# schematic.net
KiCad netlist of a schematic drawn in EAGLE
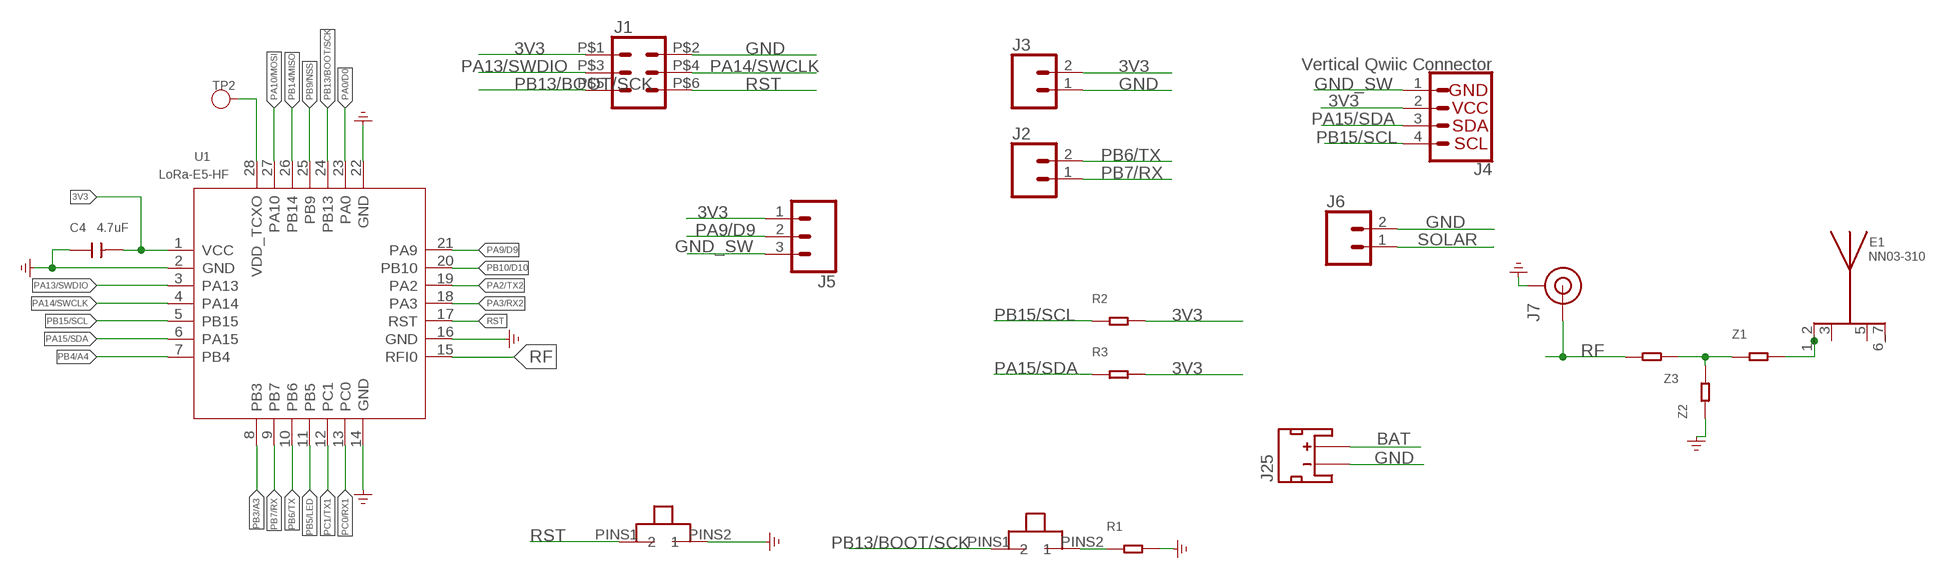
[diagram p0: schematic, sheet 1]
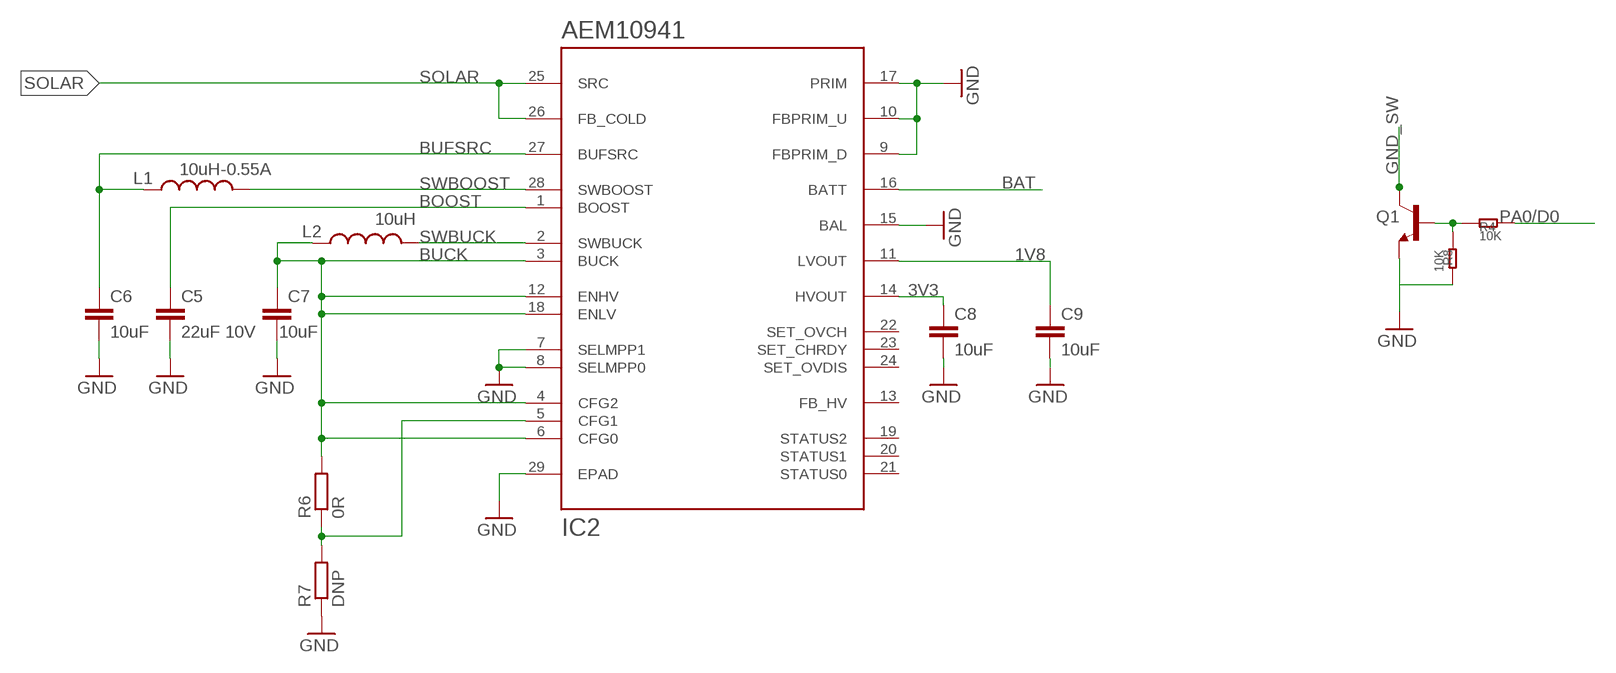
[diagram p1: schematic, sheet 2]

(export (version "E")
  (design (tool "Eeschema 10.0.6"))
  (components
    (comp (ref "C4")
      (value "4.7uF")
      (footprint "eagle-import:C0603")
      (libsource (lib "eagle-import") (part "CAP-0603"))
    )
    (comp (ref "E1")
      (value "NN03-310")
      (footprint "eagle-import:XCVR_NN03-310")
      (fields (field (name "MF") "Ignion"))
      (libsource (lib "eagle-import") (part "NN03-310"))
    )
    (comp (ref "J1")
      (value "CONN_03X2POGO_PINS")
      (footprint "eagle-import:2X3_POGO")
      (libsource (lib "eagle-import") (part "CONN_03X2POGO_PINS"))
    )
    (comp (ref "J2")
      (value "CONN_02")
      (footprint "eagle-import:1X02")
      (libsource (lib "eagle-import") (part "CONN_02"))
    )
    (comp (ref "J3")
      (value "CONN_02")
      (footprint "eagle-import:1X02")
      (libsource (lib "eagle-import") (part "CONN_02"))
    )
    (comp (ref "J4")
      (value "Vertical Qwiic Connector")
      (footprint "eagle-import:JST04_1MM_VERT")
      (libsource (lib "eagle-import") (part "QWIIC_CONNECTOR"))
    )
    (comp (ref "J5")
      (value "CONN_031X03_NO_SILK")
      (footprint "eagle-import:1X03_NO_SILK")
      (libsource (lib "eagle-import") (part "CONN_031X03_NO_SILK"))
    )
    (comp (ref "J6")
      (value "CONN_02")
      (footprint "eagle-import:1X02")
      (libsource (lib "eagle-import") (part "CONN_02"))
    )
    (comp (ref "J7")
      (value "U.FL2PIN-REDUCED-FOOTPRINT")
      (footprint "eagle-import:U.FL_REDUCED_FOOTPRINT")
      (libsource (lib "eagle-import") (part "U.FL2PIN-REDUCED-FOOTPRINT"))
    )
    (comp (ref "J25")
      (value "JST_2MM_MALE")
      (footprint "eagle-import:JST-2-SMD")
      (libsource (lib "eagle-import") (part "JST_2MM_MALE"))
    )
    (comp (ref "R1")
      (value "RES-0603")
      (footprint "eagle-import:R0603")
      (libsource (lib "eagle-import") (part "RES-0603"))
    )
    (comp (ref "R2")
      (value "RES-0603")
      (footprint "eagle-import:R0603")
      (libsource (lib "eagle-import") (part "RES-0603"))
    )
    (comp (ref "R3")
      (value "RES-0603")
      (footprint "eagle-import:R0603")
      (libsource (lib "eagle-import") (part "RES-0603"))
    )
    (comp (ref "TP2")
      (value "TEST")
      (footprint "eagle-import:TP-D45MIL")
      (fields (field (name "PARTNO") "DNP"))
      (libsource (lib "eagle-import") (part "TEST-POINT'4545'"))
    )
    (comp (ref "U$1")
      (value "TACTILE")
      (footprint "eagle-import:TACTILE")
      (libsource (lib "eagle-import") (part "TACTILE"))
    )
    (comp (ref "U$2")
      (value "TACTILE")
      (footprint "eagle-import:TACTILE")
      (libsource (lib "eagle-import") (part "TACTILE"))
    )
    (comp (ref "U1")
      (value "LoRa-E5-HF")
      (footprint "eagle-import:MOUDLE28P-1.25-12X12X2.5MM")
      (libsource (lib "eagle-import") (part "MOUDLE_LORA_E5"))
    )
    (comp (ref "Z1")
      (value "RES-0603")
      (footprint "eagle-import:R0603")
      (libsource (lib "eagle-import") (part "RES-0603"))
    )
    (comp (ref "Z2")
      (value "RES-0603")
      (footprint "eagle-import:R0603")
      (libsource (lib "eagle-import") (part "RES-0603"))
    )
    (comp (ref "Z3")
      (value "RES-0603")
      (footprint "eagle-import:R0603")
      (libsource (lib "eagle-import") (part "RES-0603"))
    )
    (comp (ref "C5")
      (value "22uF 10V")
      (footprint "eagle-import:C0603")
      (fields
        (field (name "MF") "Murata")
        (field (name "MPN") "GRM188R61A226ME15D")
        (field (name "MF_1") "TDK")
        (field (name "MPN_1") "CGA5L1X7S1A226M160AC")
      )
      (libsource (lib "eagle-import") (part "C0603_22UF"))
    )
    (comp (ref "C6")
      (value "10uF")
      (footprint "eagle-import:C0603")
      (fields
        (field (name "MF") "Taiyo Yuden")
        (field (name "MPN") "LMK107BBJ106MALT")
        (field (name "MF_1") "KEYSTONE")
        (field (name "MPN_1") "1049P")
      )
      (libsource (lib "eagle-import") (part "C0603_10UF"))
    )
    (comp (ref "C7")
      (value "10uF")
      (footprint "eagle-import:C0603")
      (fields
        (field (name "MF") "Taiyo Yuden")
        (field (name "MPN") "LMK107BBJ106MALT")
        (field (name "MF_1") "KEYSTONE")
        (field (name "MPN_1") "1049P")
      )
      (libsource (lib "eagle-import") (part "C0603_10UF"))
    )
    (comp (ref "C8")
      (value "10uF")
      (footprint "eagle-import:C0603")
      (fields
        (field (name "MF") "Taiyo Yuden")
        (field (name "MPN") "LMK107BBJ106MALT")
        (field (name "MF_1") "KEYSTONE")
        (field (name "MPN_1") "1049P")
      )
      (libsource (lib "eagle-import") (part "C0603_10UF"))
    )
    (comp (ref "C9")
      (value "10uF")
      (footprint "eagle-import:C0603")
      (fields
        (field (name "MF") "Taiyo Yuden")
        (field (name "MPN") "LMK107BBJ106MALT")
        (field (name "MF_1") "KEYSTONE")
        (field (name "MPN_1") "1049P")
      )
      (libsource (lib "eagle-import") (part "C0603_10UF"))
    )
    (comp (ref "IC2")
      (value "AEM10941")
      (footprint "eagle-import:QFN50P505X505X90-28")
      (fields (field (name "MF") "e-peas"))
      (libsource (lib "eagle-import") (part "AEM10941"))
    )
    (comp (ref "L1")
      (value "10uH-0.55A")
      (footprint "eagle-import:LPS4012")
      (fields
        (field (name "MF") "Coilcraft")
        (field (name "MPN") "LPS4012-103MRB")
        (field (name "MF_1") "BOURNS")
        (field (name "MPN_1") "SRN2009T-100M")
      )
      (libsource (lib "eagle-import") (part "L3.9X3.9_10UH_0.55A"))
    )
    (comp (ref "L2")
      (value "10uH")
      (footprint "eagle-import:L0603")
      (fields
        (field (name "MF") "TDK")
        (field (name "MPN") "MLZ1608M100WT")
        (field (name "MF_1") "TAIYO YUDEN")
        (field (name "MPN_1") "CK2125100M-T")
      )
      (libsource (lib "eagle-import") (part "L0603_10UH"))
    )
    (comp (ref "Q1")
      (value "500mA/300V")
      (footprint "eagle-import:SOT23-3")
      (libsource (lib "eagle-import") (part "TRANS_NPN-MMBTA42"))
    )
    (comp (ref "R4")
      (value "10K")
      (footprint "eagle-import:R0603")
      (libsource (lib "eagle-import") (part "RES-0603"))
    )
    (comp (ref "R6")
      (value "0R")
      (footprint "eagle-import:R0402")
      (fields (field (name "MF") "Walsin") (field (name "MPN") "WR04X1004FTL"))
      (libsource (lib "eagle-import") (part "R0402_1M"))
    )
    (comp (ref "R7")
      (value "DNP")
      (footprint "eagle-import:R0402")
      (fields (field (name "MF") "Walsin") (field (name "MPN") "WR04X1004FTL"))
      (libsource (lib "eagle-import") (part "R0402_1M"))
    )
    (comp (ref "R8")
      (value "10K")
      (footprint "eagle-import:R0603")
      (libsource (lib "eagle-import") (part "RES-0603"))
    )
  )
  (nets
    (net (code "1") (name "1V8") (class "Default")
      (node (ref "C9") (pin "1") (pinfunction "1_1") (pintype "passive"))
      (node (ref "IC2") (pin "11") (pinfunction "LVOUT_11") (pintype "bidirectional"))
    )
    (net (code "2") (name "3V3") (class "Default")
      (node (ref "C4") (pin "2") (pinfunction "2_2") (pintype "passive"))
      (node (ref "C8") (pin "1") (pinfunction "1_1") (pintype "passive"))
      (node (ref "IC2") (pin "14") (pinfunction "HVOUT_14") (pintype "bidirectional"))
      (node (ref "J1") (pin "P$1") (pinfunction "1_P$1") (pintype "bidirectional"))
      (node (ref "J3") (pin "2") (pinfunction "2_2") (pintype "passive"))
      (node (ref "J4") (pin "2") (pinfunction "2_2") (pintype "power_in"))
      (node (ref "J5") (pin "1") (pinfunction "1_1") (pintype "passive"))
      (node (ref "R2") (pin "2") (pinfunction "2_2") (pintype "passive"))
      (node (ref "R3") (pin "2") (pinfunction "2_2") (pintype "passive"))
      (node (ref "U1") (pin "1") (pinfunction "VCC_1") (pintype "bidirectional"))
    )
    (net (code "3") (name "BAT") (class "Default")
      (node (ref "IC2") (pin "16") (pinfunction "BATT_16") (pintype "bidirectional"))
      (node (ref "J25") (pin "2") (pinfunction "+_2") (pintype "bidirectional"))
    )
    (net (code "4") (name "BOOST") (class "Default")
      (node (ref "C5") (pin "1") (pinfunction "1_1") (pintype "passive"))
      (node (ref "IC2") (pin "1") (pinfunction "BOOST_1") (pintype "bidirectional"))
    )
    (net (code "5") (name "BUCK") (class "Default")
      (node (ref "C7") (pin "1") (pinfunction "1_1") (pintype "passive"))
      (node (ref "IC2") (pin "12") (pinfunction "ENHV_12") (pintype "bidirectional"))
      (node (ref "IC2") (pin "18") (pinfunction "ENLV_18") (pintype "bidirectional"))
      (node (ref "IC2") (pin "3") (pinfunction "BUCK_3") (pintype "bidirectional"))
      (node (ref "IC2") (pin "4") (pinfunction "CFG2_4") (pintype "bidirectional"))
      (node (ref "IC2") (pin "6") (pinfunction "CFG0_6") (pintype "bidirectional"))
      (node (ref "L2") (pin "1") (pinfunction "1_1") (pintype "passive"))
      (node (ref "R6") (pin "2") (pinfunction "2_2") (pintype "passive"))
    )
    (net (code "6") (name "BUFSRC") (class "Default")
      (node (ref "C6") (pin "1") (pinfunction "1_1") (pintype "passive"))
      (node (ref "IC2") (pin "27") (pinfunction "BUFSRC_27") (pintype "power_in"))
      (node (ref "L1") (pin "1") (pinfunction "1_1") (pintype "passive"))
    )
    (net (code "7") (name "GND") (class "Default")
      (node (ref "C4") (pin "1") (pinfunction "1_1") (pintype "passive"))
      (node (ref "C5") (pin "2") (pinfunction "2_2") (pintype "passive"))
      (node (ref "C6") (pin "2") (pinfunction "2_2") (pintype "passive"))
      (node (ref "C7") (pin "2") (pinfunction "2_2") (pintype "passive"))
      (node (ref "C8") (pin "2") (pinfunction "2_2") (pintype "passive"))
      (node (ref "C9") (pin "2") (pinfunction "2_2") (pintype "passive"))
      (node (ref "IC2") (pin "10") (pinfunction "FBPRIM_U_10") (pintype "bidirectional"))
      (node (ref "IC2") (pin "15") (pinfunction "BAL_15") (pintype "bidirectional"))
      (node (ref "IC2") (pin "17") (pinfunction "PRIM_17") (pintype "bidirectional"))
      (node (ref "IC2") (pin "29") (pinfunction "EPAD_29") (pintype "power_in"))
      (node (ref "IC2") (pin "7") (pinfunction "SELMPP1_7") (pintype "bidirectional"))
      (node (ref "IC2") (pin "8") (pinfunction "SELMPP0_8") (pintype "bidirectional"))
      (node (ref "IC2") (pin "9") (pinfunction "FBPRIM_D_9") (pintype "bidirectional"))
      (node (ref "J1") (pin "P$2") (pinfunction "2_P$2") (pintype "bidirectional"))
      (node (ref "J25") (pin "1") (pinfunction "-_1") (pintype "bidirectional"))
      (node (ref "J3") (pin "1") (pinfunction "1_1") (pintype "passive"))
      (node (ref "J6") (pin "2") (pinfunction "2_2") (pintype "passive"))
      (node (ref "J7") (pin "1") (pinfunction "GND_1") (pintype "bidirectional"))
      (node (ref "J7") (pin "2") (pinfunction "GND_2") (pintype "bidirectional"))
      (node (ref "Q1") (pin "2") (pinfunction "E_2") (pintype "passive"))
      (node (ref "R1") (pin "2") (pinfunction "2_2") (pintype "passive"))
      (node (ref "R7") (pin "1") (pinfunction "1_1") (pintype "passive"))
      (node (ref "R8") (pin "2") (pinfunction "2_2") (pintype "passive"))
      (node (ref "U$1") (pin "PINS2") (pinfunction "2_PINS2") (pintype "bidirectional"))
      (node (ref "U1") (pin "14") (pinfunction "GND_14") (pintype "bidirectional"))
      (node (ref "U1") (pin "16") (pinfunction "GND_16") (pintype "bidirectional"))
      (node (ref "U1") (pin "2") (pinfunction "GND_2") (pintype "bidirectional"))
      (node (ref "U1") (pin "22") (pinfunction "GND_22") (pintype "bidirectional"))
      (node (ref "Z2") (pin "1") (pinfunction "1_1") (pintype "passive"))
    )
    (net (code "8") (name "GND_SW") (class "Default")
      (node (ref "J4") (pin "1") (pinfunction "1_1") (pintype "power_in"))
      (node (ref "J5") (pin "3") (pinfunction "3_3") (pintype "passive"))
      (node (ref "Q1") (pin "3") (pinfunction "C_3") (pintype "passive"))
    )
    (net (code "9") (name "Net-(E1-1)") (class "Default")
      (node (ref "E1") (pin "1_2") (pinfunction "1_1_2") (pintype "input"))
      (node (ref "Z1") (pin "2") (pinfunction "2_2") (pintype "passive"))
    )
    (net (code "10") (name "Net-(IC2-CFG1)") (class "Default")
      (node (ref "IC2") (pin "5") (pinfunction "CFG1_5") (pintype "bidirectional"))
      (node (ref "R6") (pin "1") (pinfunction "1_1") (pintype "passive"))
      (node (ref "R7") (pin "2") (pinfunction "2_2") (pintype "passive"))
    )
    (net (code "11") (name "Net-(Q1-B)") (class "Default")
      (node (ref "Q1") (pin "1") (pinfunction "B_1") (pintype "passive"))
      (node (ref "R4") (pin "1") (pinfunction "1_1") (pintype "passive"))
      (node (ref "R8") (pin "1") (pinfunction "1_1") (pintype "passive"))
    )
    (net (code "12") (name "Net-(U$2-2)") (class "Default")
      (node (ref "R1") (pin "1") (pinfunction "1_1") (pintype "passive"))
      (node (ref "U$2") (pin "PINS2") (pinfunction "2_PINS2") (pintype "bidirectional"))
    )
    (net (code "13") (name "Net-(U1-VDD_TCXO)") (class "Default")
      (node (ref "TP2") (pin "T") (pinfunction "T_T") (pintype "bidirectional"))
      (node (ref "U1") (pin "28") (pinfunction "VDD_TCXO_28") (pintype "bidirectional"))
    )
    (net (code "14") (name "Net-(Z1-Pad1)") (class "Default")
      (node (ref "Z1") (pin "1") (pinfunction "1_1") (pintype "passive"))
      (node (ref "Z2") (pin "2") (pinfunction "2_2") (pintype "passive"))
      (node (ref "Z3") (pin "1") (pinfunction "1_1") (pintype "passive"))
    )
    (net (code "15") (name "PA0{slash}D0") (class "Default")
      (node (ref "R4") (pin "2") (pinfunction "2_2") (pintype "passive"))
      (node (ref "U1") (pin "23") (pinfunction "PA0_23") (pintype "bidirectional"))
    )
    (net (code "16") (name "PA2{slash}TX2") (class "Default")
      (node (ref "U1") (pin "19") (pinfunction "PA2_19") (pintype "bidirectional"))
    )
    (net (code "17") (name "PA3{slash}RX2") (class "Default")
      (node (ref "U1") (pin "18") (pinfunction "PA3_18") (pintype "bidirectional"))
    )
    (net (code "18") (name "PA9{slash}D9") (class "Default")
      (node (ref "J5") (pin "2") (pinfunction "2_2") (pintype "passive"))
      (node (ref "U1") (pin "21") (pinfunction "PA9_21") (pintype "bidirectional"))
    )
    (net (code "19") (name "PA10{slash}MOSI") (class "Default")
      (node (ref "U1") (pin "27") (pinfunction "PA10_27") (pintype "bidirectional"))
    )
    (net (code "20") (name "PA13{slash}SWDIO") (class "Default")
      (node (ref "J1") (pin "P$3") (pinfunction "3_P$3") (pintype "bidirectional"))
      (node (ref "U1") (pin "3") (pinfunction "PA13_3") (pintype "bidirectional"))
    )
    (net (code "21") (name "PA14{slash}SWCLK") (class "Default")
      (node (ref "J1") (pin "P$4") (pinfunction "4_P$4") (pintype "bidirectional"))
      (node (ref "U1") (pin "4") (pinfunction "PA14_4") (pintype "bidirectional"))
    )
    (net (code "22") (name "PA15{slash}SDA") (class "Default")
      (node (ref "J4") (pin "3") (pinfunction "3_3") (pintype "passive"))
      (node (ref "R3") (pin "1") (pinfunction "1_1") (pintype "passive"))
      (node (ref "U1") (pin "6") (pinfunction "PA15_6") (pintype "bidirectional"))
    )
    (net (code "23") (name "PB3{slash}A3") (class "Default")
      (node (ref "U1") (pin "8") (pinfunction "PB3_8") (pintype "bidirectional"))
    )
    (net (code "24") (name "PB4{slash}A4") (class "Default")
      (node (ref "U1") (pin "7") (pinfunction "PB4_7") (pintype "bidirectional"))
    )
    (net (code "25") (name "PB5{slash}LED") (class "Default")
      (node (ref "U1") (pin "11") (pinfunction "PB5_11") (pintype "bidirectional"))
    )
    (net (code "26") (name "PB6{slash}TX") (class "Default")
      (node (ref "J2") (pin "2") (pinfunction "2_2") (pintype "passive"))
      (node (ref "U1") (pin "10") (pinfunction "PB6_10") (pintype "bidirectional"))
    )
    (net (code "27") (name "PB7{slash}RX") (class "Default")
      (node (ref "J2") (pin "1") (pinfunction "1_1") (pintype "passive"))
      (node (ref "U1") (pin "9") (pinfunction "PB7_9") (pintype "bidirectional"))
    )
    (net (code "28") (name "PB9{slash}NSS") (class "Default")
      (node (ref "U1") (pin "25") (pinfunction "PB9_25") (pintype "bidirectional"))
    )
    (net (code "29") (name "PB10{slash}D10") (class "Default")
      (node (ref "U1") (pin "20") (pinfunction "PB10_20") (pintype "bidirectional"))
    )
    (net (code "30") (name "PB13{slash}BOOT{slash}SCK") (class "Default")
      (node (ref "J1") (pin "P$5") (pinfunction "5_P$5") (pintype "bidirectional"))
      (node (ref "U$2") (pin "PINS1") (pinfunction "1_PINS1") (pintype "bidirectional"))
      (node (ref "U1") (pin "24") (pinfunction "PB13_24") (pintype "bidirectional"))
    )
    (net (code "31") (name "PB14{slash}MISO") (class "Default")
      (node (ref "U1") (pin "26") (pinfunction "PB14_26") (pintype "bidirectional"))
    )
    (net (code "32") (name "PB15{slash}SCL") (class "Default")
      (node (ref "J4") (pin "4") (pinfunction "4_4") (pintype "passive"))
      (node (ref "R2") (pin "1") (pinfunction "1_1") (pintype "passive"))
      (node (ref "U1") (pin "5") (pinfunction "PB15_5") (pintype "bidirectional"))
    )
    (net (code "33") (name "PC0{slash}RX1") (class "Default")
      (node (ref "U1") (pin "13") (pinfunction "PC0_13") (pintype "bidirectional"))
    )
    (net (code "34") (name "PC1{slash}TX1") (class "Default")
      (node (ref "U1") (pin "12") (pinfunction "PC1_12") (pintype "bidirectional"))
    )
    (net (code "35") (name "RF") (class "Default")
      (node (ref "J7") (pin "FEED") (pinfunction "SIGNAL_FEED") (pintype "bidirectional"))
      (node (ref "U1") (pin "15") (pinfunction "RFI0_15") (pintype "bidirectional"))
      (node (ref "Z3") (pin "2") (pinfunction "2_2") (pintype "passive"))
    )
    (net (code "36") (name "RST") (class "Default")
      (node (ref "J1") (pin "P$6") (pinfunction "6_P$6") (pintype "bidirectional"))
      (node (ref "U$1") (pin "PINS1") (pinfunction "1_PINS1") (pintype "bidirectional"))
      (node (ref "U1") (pin "17") (pinfunction "RST_17") (pintype "bidirectional"))
    )
    (net (code "37") (name "SOLAR") (class "Default")
      (node (ref "IC2") (pin "25") (pinfunction "SRC_25") (pintype "power_in"))
      (node (ref "IC2") (pin "26") (pinfunction "FB_COLD_26") (pintype "input"))
      (node (ref "J6") (pin "1") (pinfunction "1_1") (pintype "passive"))
    )
    (net (code "38") (name "SWBOOST") (class "Default")
      (node (ref "IC2") (pin "28") (pinfunction "SWBOOST_28") (pintype "power_in"))
      (node (ref "L1") (pin "2") (pinfunction "2_2") (pintype "passive"))
    )
    (net (code "39") (name "SWBUCK") (class "Default")
      (node (ref "IC2") (pin "2") (pinfunction "SWBUCK_2") (pintype "bidirectional"))
      (node (ref "L2") (pin "2") (pinfunction "2_2") (pintype "passive"))
    )
    (net (code "40") (name "unconnected-(E1-6-Pad6_7)") (class "Default")
      (node (ref "E1") (pin "6_7") (pinfunction "6_6_7") (pintype "passive"))
    )
    (net (code "41") (name "unconnected-(E1-Pad3)") (class "Default")
      (node (ref "E1") (pin "3") (pinfunction "3_3") (pintype "passive"))
    )
    (net (code "42") (name "unconnected-(E1-Pad5)") (class "Default")
      (node (ref "E1") (pin "5") (pinfunction "5_5") (pintype "passive"))
    )
    (net (code "43") (name "unconnected-(IC2-FB_HV-Pad13)") (class "Default")
      (node (ref "IC2") (pin "13") (pinfunction "FB_HV_13") (pintype "bidirectional"))
    )
    (net (code "44") (name "unconnected-(IC2-SET_CHRDY-Pad23)") (class "Default")
      (node (ref "IC2") (pin "23") (pinfunction "SET_CHRDY_23") (pintype "bidirectional"))
    )
    (net (code "45") (name "unconnected-(IC2-SET_OVCH-Pad22)") (class "Default")
      (node (ref "IC2") (pin "22") (pinfunction "SET_OVCH_22") (pintype "bidirectional"))
    )
    (net (code "46") (name "unconnected-(IC2-SET_OVDIS-Pad24)") (class "Default")
      (node (ref "IC2") (pin "24") (pinfunction "SET_OVDIS_24") (pintype "bidirectional"))
    )
    (net (code "47") (name "unconnected-(IC2-STATUS0-Pad21)") (class "Default")
      (node (ref "IC2") (pin "21") (pinfunction "STATUS0_21") (pintype "bidirectional"))
    )
    (net (code "48") (name "unconnected-(IC2-STATUS1-Pad20)") (class "Default")
      (node (ref "IC2") (pin "20") (pinfunction "STATUS1_20") (pintype "bidirectional"))
    )
    (net (code "49") (name "unconnected-(IC2-STATUS2-Pad19)") (class "Default")
      (node (ref "IC2") (pin "19") (pinfunction "STATUS2_19") (pintype "bidirectional"))
    )
    (net (code "50") (name "unconnected-(J25-PAD1-PadNC1)") (class "Default")
      (node (ref "J25") (pin "NC1") (pinfunction "PAD1_NC1") (pintype "bidirectional"))
    )
    (net (code "51") (name "unconnected-(J25-PAD2-PadNC2)") (class "Default")
      (node (ref "J25") (pin "NC2") (pinfunction "PAD2_NC2") (pintype "bidirectional"))
    )
  )
)
